# tx.net
KiCad netlist of a schematic drawn in Altium Designer
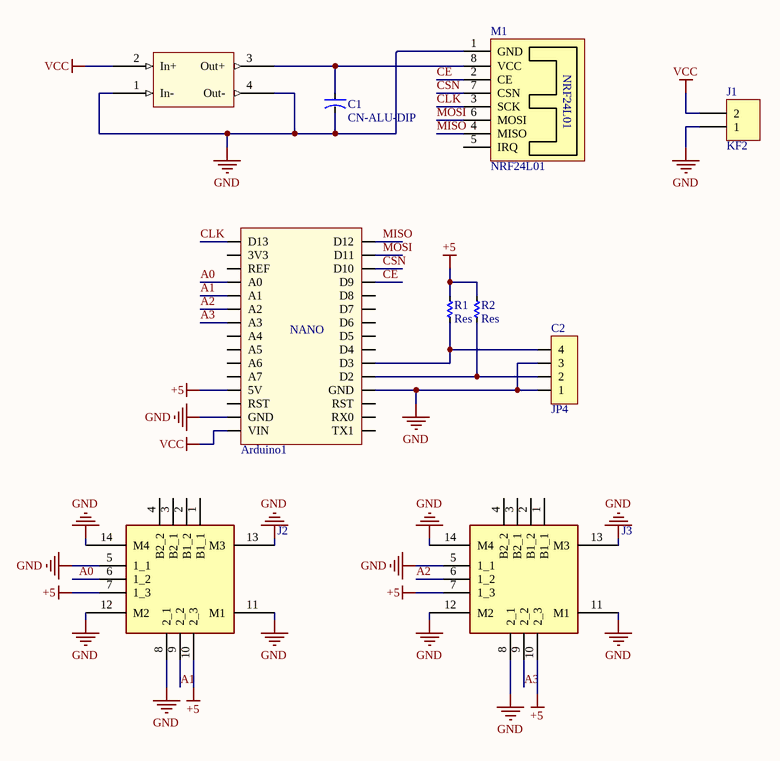
[diagram p0: tx.SchDoc]

(export (version "E")
  (design (tool "Eeschema 10.0.6"))
  (components
    (comp (ref "Arduino1")
      (value "Arduino Nano")
      (footprint "Arduino Nano")
      (description "Arduino NANO")
      (libsource (lib "LIBRARY") (part "Arduino Nano"))
    )
    (comp (ref "C1")
      (value "CN-ALU-DIP")
      (footprint "CA-ALU-6.3")
      (description "Capacitor (Semiconductor SIM Model)")
      (fields (field (name "PUBLISHER") "Altium Limited"))
      (libsource (lib "LIBRARY") (part "CN-ALU-DIP"))
    )
    (comp (ref "C2")
      (value "JP4")
      (footprint "JP4-C1T")
      (description "WR-PHD 2.54 mm Angled Socket Header")
      (fields
        (field (name "MANUFACTURER") "Würth Elektronik eiSos GmbH")
        (field (name "PARTNO") "613004143121")
        (field (name "CREATED BY") "Karrer Zheng")
      )
      (libsource (lib "LIBRARY") (part "JP4"))
    )
    (comp (ref "J1")
      (value "KF2")
      (footprint "KF2-5.08")
      (fields
        (field (name "MANUFACTURER") "Würth Elektronik eiSos GmbH")
        (field (name "PARTNO") "691103110002")
        (field (name "CREATED BY") "Karrer Zheng")
      )
      (libsource (lib "LIBRARY") (part "KF2"))
    )
    (comp (ref "J2")
      (value "RKJXV1224005")
      (footprint "RKJXV1224005")
      (description "Joystick")
      (fields
        (field (name "MOUSER PART NUMBER") "688-RKJXV1224005")
        (field (name "RS PART NUMBER") "1239578")
      )
      (libsource (lib "0503") (part "RKJXV1224005"))
    )
    (comp (ref "J3")
      (value "RKJXV1224005")
      (footprint "RKJXV1224005")
      (description "Joystick")
      (fields
        (field (name "MOUSER PART NUMBER") "688-RKJXV1224005")
        (field (name "RS PART NUMBER") "1239578")
      )
      (libsource (lib "0503") (part "RKJXV1224005"))
    )
    (comp (ref "M1") (value "NRF24L01") (footprint "NRF24L01") (libsource (lib "LIBRARY") (part "NRF24L01")))
    (comp (ref "MP1")
      (value "MP2307 DC-DC Switching Buck Step-Down Module")
      (footprint "Mini360")
      (libsource (lib "0503") (part "MP2307 Module"))
    )
    (comp (ref "R1")
      (value "Res")
      (footprint "RES-SMD-1206")
      (description "Resistor")
      (fields
        (field (name "MANUFACTURER") "Generic Components")
        (field (name "PUBLISHER") "Altium Hobart Technology Centre")
      )
      (libsource (lib "LIBRARY") (part "Res-SMD"))
    )
    (comp (ref "R2")
      (value "Res")
      (footprint "RES-SMD-1206")
      (description "Resistor")
      (fields
        (field (name "MANUFACTURER") "Generic Components")
        (field (name "PUBLISHER") "Altium Hobart Technology Centre")
      )
      (libsource (lib "LIBRARY") (part "Res-SMD"))
    )
  )
  (nets
    (net (code "1") (name "+5") (class "Default")
      (node (ref "Arduino1") (pin "5V") (pinfunction "5V_5V") (pintype "passive"))
      (node (ref "J2") (pin "10") (pinfunction "2_3_10") (pintype "passive"))
      (node (ref "J2") (pin "7") (pinfunction "1_3_7") (pintype "passive"))
      (node (ref "J3") (pin "10") (pinfunction "2_3_10") (pintype "passive"))
      (node (ref "J3") (pin "7") (pinfunction "1_3_7") (pintype "passive"))
      (node (ref "R1") (pin "1") (pinfunction "1_1") (pintype "passive"))
      (node (ref "R2") (pin "1") (pinfunction "1_1") (pintype "passive"))
    )
    (net (code "2") (name "/A0") (class "Default")
      (node (ref "Arduino1") (pin "A0") (pinfunction "A0_A0") (pintype "passive"))
      (node (ref "J2") (pin "6") (pinfunction "1_2_6") (pintype "passive"))
    )
    (net (code "3") (name "/A1") (class "Default")
      (node (ref "Arduino1") (pin "A1") (pinfunction "A1_A1") (pintype "passive"))
      (node (ref "J2") (pin "9") (pinfunction "2_2_9") (pintype "passive"))
    )
    (net (code "4") (name "/A2") (class "Default")
      (node (ref "Arduino1") (pin "A2") (pinfunction "A2_A2") (pintype "passive"))
      (node (ref "J3") (pin "6") (pinfunction "1_2_6") (pintype "passive"))
    )
    (net (code "5") (name "/A3") (class "Default")
      (node (ref "Arduino1") (pin "A3") (pinfunction "A3_A3") (pintype "passive"))
      (node (ref "J3") (pin "9") (pinfunction "2_2_9") (pintype "passive"))
    )
    (net (code "6") (name "/CE") (class "Default")
      (node (ref "Arduino1") (pin "D9") (pinfunction "D9_D9") (pintype "passive"))
      (node (ref "M1") (pin "2") (pinfunction "CE_2") (pintype "passive"))
    )
    (net (code "7") (name "/CLK") (class "Default")
      (node (ref "Arduino1") (pin "D13") (pinfunction "D13_D13") (pintype "passive"))
      (node (ref "M1") (pin "3") (pinfunction "SCK_3") (pintype "passive"))
    )
    (net (code "8") (name "/CSN") (class "Default")
      (node (ref "Arduino1") (pin "D10") (pinfunction "D10_D10") (pintype "passive"))
      (node (ref "M1") (pin "7") (pinfunction "CSN_7") (pintype "passive"))
    )
    (net (code "9") (name "/MISO") (class "Default")
      (node (ref "Arduino1") (pin "D12") (pinfunction "D12_D12") (pintype "passive"))
      (node (ref "M1") (pin "4") (pinfunction "MISO_4") (pintype "passive"))
    )
    (net (code "10") (name "/MOSI") (class "Default")
      (node (ref "Arduino1") (pin "D11") (pinfunction "D11_D11") (pintype "passive"))
      (node (ref "M1") (pin "6") (pinfunction "MOSI_6") (pintype "passive"))
    )
    (net (code "11") (name "GND") (class "Default")
      (node (ref "Arduino1") (pin "GND") (pinfunction "GND_GND") (pintype "passive"))
      (node (ref "C1") (pin "2") (pinfunction "2_2") (pintype "passive"))
      (node (ref "C2") (pin "1") (pinfunction "1_1") (pintype "passive"))
      (node (ref "C2") (pin "3") (pinfunction "3_3") (pintype "passive"))
      (node (ref "J1") (pin "1") (pinfunction "1_1") (pintype "passive"))
      (node (ref "J2") (pin "11") (pinfunction "M1_11") (pintype "passive"))
      (node (ref "J2") (pin "12") (pinfunction "M2_12") (pintype "passive"))
      (node (ref "J2") (pin "13") (pinfunction "M3_13") (pintype "passive"))
      (node (ref "J2") (pin "14") (pinfunction "M4_14") (pintype "passive"))
      (node (ref "J2") (pin "5") (pinfunction "1_1_5") (pintype "passive"))
      (node (ref "J2") (pin "8") (pinfunction "2_1_8") (pintype "passive"))
      (node (ref "J3") (pin "11") (pinfunction "M1_11") (pintype "passive"))
      (node (ref "J3") (pin "12") (pinfunction "M2_12") (pintype "passive"))
      (node (ref "J3") (pin "13") (pinfunction "M3_13") (pintype "passive"))
      (node (ref "J3") (pin "14") (pinfunction "M4_14") (pintype "passive"))
      (node (ref "J3") (pin "5") (pinfunction "1_1_5") (pintype "passive"))
      (node (ref "J3") (pin "8") (pinfunction "2_1_8") (pintype "passive"))
      (node (ref "M1") (pin "1") (pinfunction "GND_1") (pintype "passive"))
      (node (ref "MP1") (pin "1") (pinfunction "In-_1") (pintype "input"))
      (node (ref "MP1") (pin "4") (pinfunction "Out-_4") (pintype "output"))
    )
    (net (code "12") (name "Net-(Arduino1-PadD2)") (class "Default")
      (node (ref "Arduino1") (pin "D2") (pinfunction "D2_D2") (pintype "passive"))
      (node (ref "C2") (pin "2") (pinfunction "2_2") (pintype "passive"))
      (node (ref "R2") (pin "2") (pinfunction "2_2") (pintype "passive"))
    )
    (net (code "13") (name "Net-(Arduino1-PadD3)") (class "Default")
      (node (ref "Arduino1") (pin "D3") (pinfunction "D3_D3") (pintype "passive"))
      (node (ref "C2") (pin "4") (pinfunction "4_4") (pintype "passive"))
      (node (ref "R1") (pin "2") (pinfunction "2_2") (pintype "passive"))
    )
    (net (code "14") (name "Net-(M1-VCC)") (class "Default")
      (node (ref "C1") (pin "1") (pinfunction "1_1") (pintype "passive"))
      (node (ref "M1") (pin "8") (pinfunction "VCC_8") (pintype "passive"))
      (node (ref "MP1") (pin "3") (pinfunction "Out+_3") (pintype "output"))
    )
    (net (code "15") (name "VCC") (class "Default")
      (node (ref "Arduino1") (pin "VIN") (pinfunction "VIN_VIN") (pintype "passive"))
      (node (ref "J1") (pin "2") (pinfunction "2_2") (pintype "passive"))
      (node (ref "MP1") (pin "2") (pinfunction "In+_2") (pintype "input"))
    )
    (net (code "16") (name "unconnected-(Arduino1-Pad3V3)") (class "Default")
      (node (ref "Arduino1") (pin "3V3") (pinfunction "3V3_3V3") (pintype "passive"))
    )
    (net (code "17") (name "unconnected-(Arduino1-PadA4)") (class "Default")
      (node (ref "Arduino1") (pin "A4") (pinfunction "A4_A4") (pintype "passive"))
    )
    (net (code "18") (name "unconnected-(Arduino1-PadA5)") (class "Default")
      (node (ref "Arduino1") (pin "A5") (pinfunction "A5_A5") (pintype "passive"))
    )
    (net (code "19") (name "unconnected-(Arduino1-PadA6)") (class "Default")
      (node (ref "Arduino1") (pin "A6") (pinfunction "A6_A6") (pintype "passive"))
    )
    (net (code "20") (name "unconnected-(Arduino1-PadA7)") (class "Default")
      (node (ref "Arduino1") (pin "A7") (pinfunction "A7_A7") (pintype "passive"))
    )
    (net (code "21") (name "unconnected-(Arduino1-PadD4)") (class "Default")
      (node (ref "Arduino1") (pin "D4") (pinfunction "D4_D4") (pintype "passive"))
    )
    (net (code "22") (name "unconnected-(Arduino1-PadD5)") (class "Default")
      (node (ref "Arduino1") (pin "D5") (pinfunction "D5_D5") (pintype "passive"))
    )
    (net (code "23") (name "unconnected-(Arduino1-PadD6)") (class "Default")
      (node (ref "Arduino1") (pin "D6") (pinfunction "D6_D6") (pintype "passive"))
    )
    (net (code "24") (name "unconnected-(Arduino1-PadD7)") (class "Default")
      (node (ref "Arduino1") (pin "D7") (pinfunction "D7_D7") (pintype "passive"))
    )
    (net (code "25") (name "unconnected-(Arduino1-PadD8)") (class "Default")
      (node (ref "Arduino1") (pin "D8") (pinfunction "D8_D8") (pintype "passive"))
    )
    (net (code "26") (name "unconnected-(Arduino1-PadREF)") (class "Default")
      (node (ref "Arduino1") (pin "REF") (pinfunction "REF_REF") (pintype "passive"))
    )
    (net (code "27") (name "unconnected-(Arduino1-PadRST)") (class "Default")
      (node (ref "Arduino1") (pin "RST") (pinfunction "RST_RST") (pintype "passive"))
    )
    (net (code "28") (name "unconnected-(Arduino1-PadRST)_1") (class "Default")
      (node (ref "Arduino1") (pin "RST") (pinfunction "RST_RST") (pintype "passive"))
    )
    (net (code "29") (name "unconnected-(Arduino1-PadRX0)") (class "Default")
      (node (ref "Arduino1") (pin "RX0") (pinfunction "RX0_RX0") (pintype "passive"))
    )
    (net (code "30") (name "unconnected-(Arduino1-PadTX1)") (class "Default")
      (node (ref "Arduino1") (pin "TX1") (pinfunction "TX1_TX1") (pintype "passive"))
    )
    (net (code "31") (name "unconnected-(J2-B1_1-Pad1)") (class "Default")
      (node (ref "J2") (pin "1") (pinfunction "B1_1_1") (pintype "passive"))
    )
    (net (code "32") (name "unconnected-(J2-B1_2-Pad2)") (class "Default")
      (node (ref "J2") (pin "2") (pinfunction "B1_2_2") (pintype "passive"))
    )
    (net (code "33") (name "unconnected-(J2-B2_1-Pad3)") (class "Default")
      (node (ref "J2") (pin "3") (pinfunction "B2_1_3") (pintype "passive"))
    )
    (net (code "34") (name "unconnected-(J2-B2_2-Pad4)") (class "Default")
      (node (ref "J2") (pin "4") (pinfunction "B2_2_4") (pintype "passive"))
    )
    (net (code "35") (name "unconnected-(J3-B1_1-Pad1)") (class "Default")
      (node (ref "J3") (pin "1") (pinfunction "B1_1_1") (pintype "passive"))
    )
    (net (code "36") (name "unconnected-(J3-B1_2-Pad2)") (class "Default")
      (node (ref "J3") (pin "2") (pinfunction "B1_2_2") (pintype "passive"))
    )
    (net (code "37") (name "unconnected-(J3-B2_1-Pad3)") (class "Default")
      (node (ref "J3") (pin "3") (pinfunction "B2_1_3") (pintype "passive"))
    )
    (net (code "38") (name "unconnected-(J3-B2_2-Pad4)") (class "Default")
      (node (ref "J3") (pin "4") (pinfunction "B2_2_4") (pintype "passive"))
    )
    (net (code "39") (name "unconnected-(M1-IRQ-Pad5)") (class "Default")
      (node (ref "M1") (pin "5") (pinfunction "IRQ_5") (pintype "passive"))
    )
  )
)
